# Communication_and_peripherals_ETH.net
KiCad netlist of a schematic drawn in Altium Designer
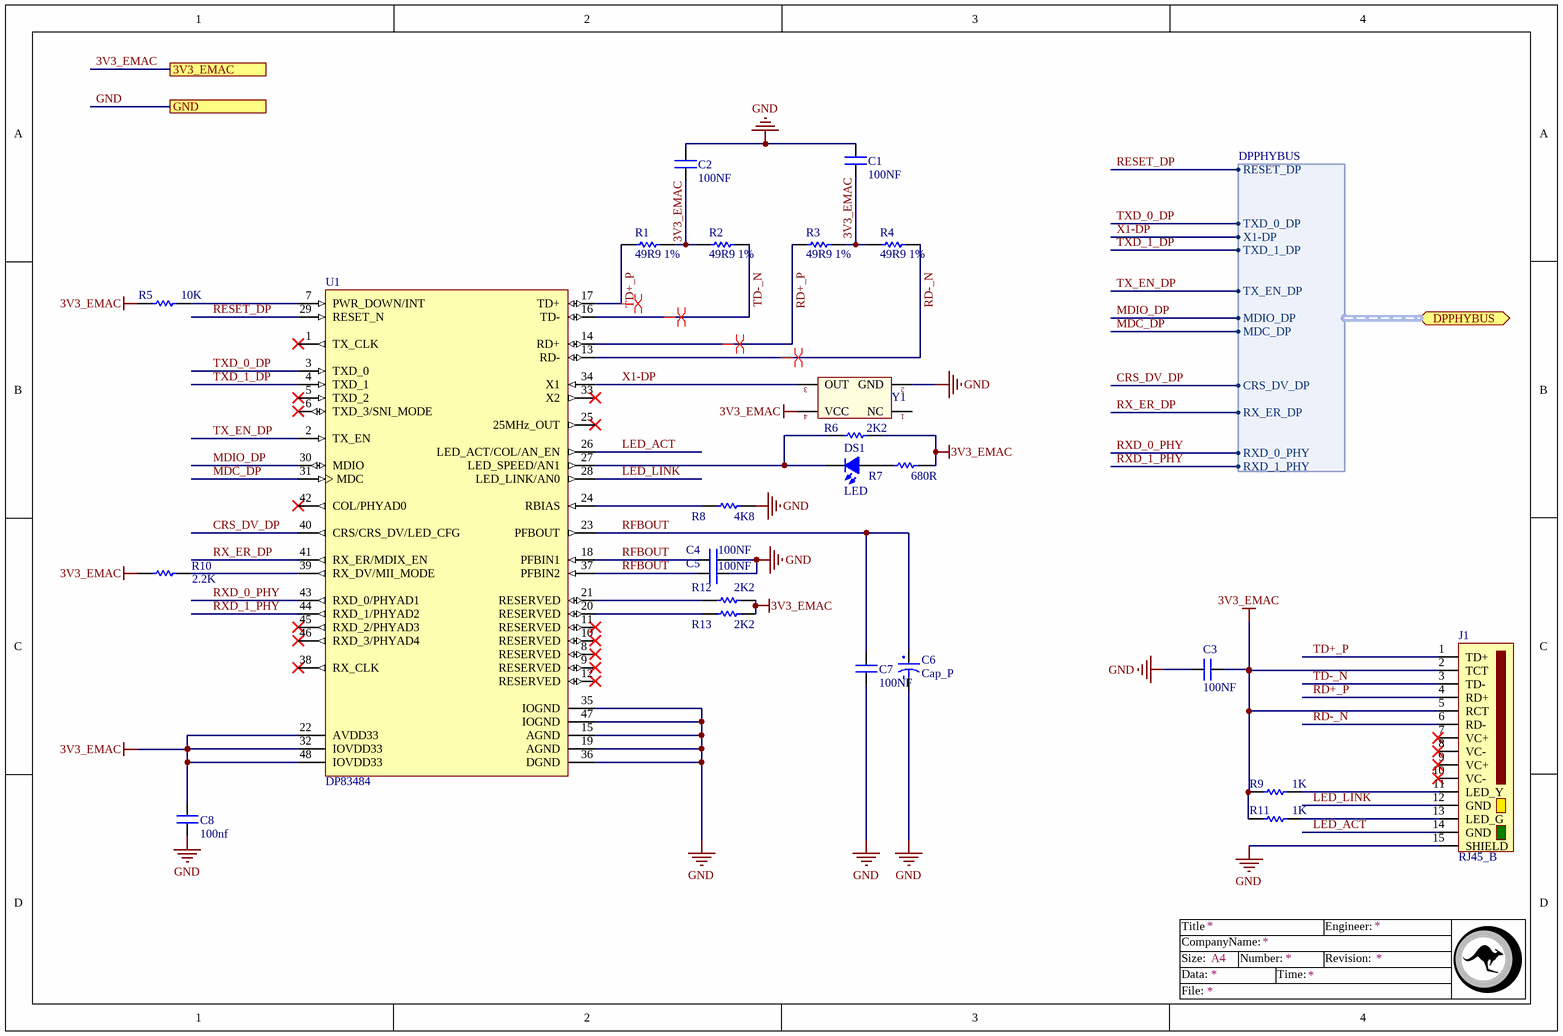
[diagram p0: Communication and peripherals ETH.SchDoc]

(export (version "E")
  (design (tool "Eeschema 10.0.6"))
  (components
    (comp (ref "C1")
      (value "100NF")
      (footprint "Cap0805")
      (description "Surface mount Capacitor")
      (libsource (lib "PMLIB2020") (part "Cap"))
    )
    (comp (ref "C2")
      (value "100NF")
      (footprint "Cap0805")
      (description "Surface mount Capacitor")
      (libsource (lib "PMLIB2020") (part "Cap"))
    )
    (comp (ref "C3")
      (value "100NF")
      (footprint "Cap0805")
      (description "Surface mount Capacitor")
      (libsource (lib "PMLIB2020") (part "Cap"))
    )
    (comp (ref "C4")
      (value "100NF")
      (footprint "Cap0805")
      (description "Surface mount Capacitor")
      (libsource (lib "PMLIB2020") (part "Cap"))
    )
    (comp (ref "C5")
      (value "100NF")
      (footprint "Cap0805")
      (description "Surface mount Capacitor")
      (libsource (lib "PMLIB2020") (part "Cap"))
    )
    (comp (ref "C6")
      (value "Cap_P")
      (footprint "Cap_4mm")
      (description "Polarity")
      (libsource (lib "PMLIB2020") (part "Cap_P"))
    )
    (comp (ref "C7")
      (value "100NF")
      (footprint "Cap0805")
      (description "Surface mount Capacitor")
      (libsource (lib "PMLIB2020") (part "Cap"))
    )
    (comp (ref "C8")
      (value "100nf")
      (footprint "Cap0805")
      (description "Surface mount Capacitor")
      (libsource (lib "PMLIB2020") (part "Cap"))
    )
    (comp (ref "DS1") (value "LED") (footprint "Led0805") (libsource (lib "PMLIB2020") (part "LED")))
    (comp (ref "J1")
      (value "RJ45_B")
      (footprint "RJ45_B")
      (description "Ethernet Connector")
      (libsource (lib "PMLIB2020") (part "RJ45_B"))
    )
    (comp (ref "R1")
      (value "49R9 1%")
      (footprint "R0805")
      (description "Resistor")
      (libsource (lib "PMLIB2020") (part "Resistor"))
    )
    (comp (ref "R2")
      (value "49R9 1%")
      (footprint "R0805")
      (description "Resistor")
      (libsource (lib "PMLIB2020") (part "Resistor"))
    )
    (comp (ref "R3")
      (value "49R9 1%")
      (footprint "R0805")
      (description "Resistor")
      (libsource (lib "PMLIB2020") (part "Resistor"))
    )
    (comp (ref "R4")
      (value "49R9 1%")
      (footprint "R0805")
      (description "Resistor")
      (libsource (lib "PMLIB2020") (part "Resistor"))
    )
    (comp (ref "R5")
      (value "10K")
      (footprint "R0805")
      (description "Resistor")
      (libsource (lib "PMLIB2020") (part "Resistor"))
    )
    (comp (ref "R6")
      (value "2K2")
      (footprint "R0805")
      (description "Resistor")
      (libsource (lib "PMLIB2020") (part "Resistor"))
    )
    (comp (ref "R7")
      (value "680R")
      (footprint "R0805")
      (description "Resistor")
      (libsource (lib "PMLIB2020") (part "Resistor"))
    )
    (comp (ref "R8")
      (value "4K8")
      (footprint "R0805")
      (description "Resistor")
      (libsource (lib "PMLIB2020") (part "Resistor"))
    )
    (comp (ref "R9")
      (value "1K")
      (footprint "R0805")
      (description "Resistor")
      (libsource (lib "PMLIB2020") (part "Resistor"))
    )
    (comp (ref "R10")
      (value "2.2K")
      (footprint "R0805")
      (description "Resistor")
      (libsource (lib "PMLIB2020") (part "Resistor"))
    )
    (comp (ref "R11")
      (value "1K")
      (footprint "R0805")
      (description "Resistor")
      (libsource (lib "PMLIB2020") (part "Resistor"))
    )
    (comp (ref "R12")
      (value "2K2")
      (footprint "R0805")
      (description "Resistor")
      (libsource (lib "PMLIB2020") (part "Resistor"))
    )
    (comp (ref "R13")
      (value "2K2")
      (footprint "R0805")
      (description "Resistor")
      (libsource (lib "PMLIB2020") (part "Resistor"))
    )
    (comp (ref "U1")
      (value "DP83484")
      (footprint "DP83484")
      (description "Ethernet PHY")
      (libsource (lib "PMLIB2020") (part "DP83484"))
    )
    (comp (ref "Y1")
      (value "Oscillator")
      (footprint "Crystall 50Mhz")
      (libsource (lib "PMLIB2020") (part "Oscillator"))
    )
  )
  (nets
    (net (code "2") (name "/CRS_DV_DP") (class "Default")
      (node (ref "U1") (pin "40") (pinfunction "CRS/CRS_DV/LED_CFG_40") (pintype "output"))
    )
    (net (code "3") (name "/LED_ACT") (class "Default")
      (node (ref "J1") (pin "14") (pinfunction "GND_14") (pintype "passive"))
      (node (ref "U1") (pin "26") (pinfunction "LED_ACT/COL/AN_EN_26") (pintype "output"))
    )
    (net (code "4") (name "/LED_LINK") (class "Default")
      (node (ref "J1") (pin "12") (pinfunction "GND_12") (pintype "passive"))
      (node (ref "U1") (pin "28") (pinfunction "LED_LINK/AN0_28") (pintype "output"))
    )
    (net (code "5") (name "/MDC_DP") (class "Default")
      (node (ref "U1") (pin "31") (pinfunction "MDC_31") (pintype "input"))
    )
    (net (code "6") (name "/MDIO_DP") (class "Default")
      (node (ref "U1") (pin "30") (pinfunction "MDIO_30") (pintype "bidirectional"))
    )
    (net (code "7") (name "/RD+_P") (class "Default")
      (node (ref "J1") (pin "4") (pinfunction "RD+_4") (pintype "passive"))
      (node (ref "R3") (pin "1") (pinfunction "1_1") (pintype "passive"))
      (node (ref "U1") (pin "14") (pinfunction "RD+_14") (pintype "bidirectional"))
    )
    (net (code "8") (name "/RD-_N") (class "Default")
      (node (ref "J1") (pin "6") (pinfunction "RD-_6") (pintype "passive"))
      (node (ref "R4") (pin "2") (pinfunction "2_2") (pintype "passive"))
      (node (ref "U1") (pin "13") (pinfunction "RD-_13") (pintype "bidirectional"))
    )
    (net (code "9") (name "/RESET_DP") (class "Default")
      (node (ref "U1") (pin "29") (pinfunction "RESET_N_29") (pintype "input"))
    )
    (net (code "10") (name "/RFBOUT") (class "Default")
      (node (ref "C4") (pin "1") (pinfunction "1_1") (pintype "passive"))
      (node (ref "C5") (pin "1") (pinfunction "1_1") (pintype "passive"))
      (node (ref "C6") (pin "2") (pinfunction "2_2") (pintype "passive"))
      (node (ref "C7") (pin "2") (pinfunction "2_2") (pintype "passive"))
      (node (ref "U1") (pin "18") (pinfunction "PFBIN1_18") (pintype "input"))
      (node (ref "U1") (pin "23") (pinfunction "PFBOUT_23") (pintype "output"))
      (node (ref "U1") (pin "37") (pinfunction "PFBIN2_37") (pintype "input"))
    )
    (net (code "11") (name "/RXD_0_PHY") (class "Default")
      (node (ref "U1") (pin "43") (pinfunction "RXD_0/PHYAD1_43") (pintype "output"))
    )
    (net (code "12") (name "/RXD_1_PHY") (class "Default")
      (node (ref "U1") (pin "44") (pinfunction "RXD_1/PHYAD2_44") (pintype "output"))
    )
    (net (code "13") (name "/RX_ER_DP") (class "Default")
      (node (ref "U1") (pin "41") (pinfunction "RX_ER/MDIX_EN_41") (pintype "output"))
    )
    (net (code "14") (name "/TD+_P") (class "Default")
      (node (ref "J1") (pin "1") (pinfunction "TD+_1") (pintype "passive"))
      (node (ref "R1") (pin "1") (pinfunction "1_1") (pintype "passive"))
      (node (ref "U1") (pin "17") (pinfunction "TD+_17") (pintype "bidirectional"))
    )
    (net (code "15") (name "/TD-_N") (class "Default")
      (node (ref "J1") (pin "3") (pinfunction "TD-_3") (pintype "passive"))
      (node (ref "R2") (pin "2") (pinfunction "2_2") (pintype "passive"))
      (node (ref "U1") (pin "16") (pinfunction "TD-_16") (pintype "bidirectional"))
    )
    (net (code "16") (name "/TXD_0_DP") (class "Default")
      (node (ref "U1") (pin "3") (pinfunction "TXD_0_3") (pintype "input"))
    )
    (net (code "17") (name "/TXD_1_DP") (class "Default")
      (node (ref "U1") (pin "4") (pinfunction "TXD_1_4") (pintype "input"))
    )
    (net (code "18") (name "/TX_EN_DP") (class "Default")
      (node (ref "U1") (pin "2") (pinfunction "TX_EN_2") (pintype "input"))
    )
    (net (code "19") (name "/X1-DP") (class "Default")
      (node (ref "U1") (pin "34") (pinfunction "X1_34") (pintype "input"))
      (node (ref "Y1") (pin "3") (pinfunction "OUT_3") (pintype "passive"))
    )
    (net (code "21") (name "3V3_EMAC") (class "Default")
      (node (ref "C1") (pin "1") (pinfunction "1_1") (pintype "passive"))
      (node (ref "C2") (pin "1") (pinfunction "1_1") (pintype "passive"))
      (node (ref "C3") (pin "1") (pinfunction "1_1") (pintype "passive"))
      (node (ref "C8") (pin "2") (pinfunction "2_2") (pintype "passive"))
      (node (ref "J1") (pin "2") (pinfunction "TCT_2") (pintype "passive"))
      (node (ref "J1") (pin "5") (pinfunction "RCT_5") (pintype "passive"))
      (node (ref "R1") (pin "2") (pinfunction "2_2") (pintype "passive"))
      (node (ref "R10") (pin "2") (pinfunction "2_2") (pintype "passive"))
      (node (ref "R11") (pin "1") (pinfunction "1_1") (pintype "passive"))
      (node (ref "R12") (pin "1") (pinfunction "1_1") (pintype "passive"))
      (node (ref "R13") (pin "1") (pinfunction "1_1") (pintype "passive"))
      (node (ref "R2") (pin "1") (pinfunction "1_1") (pintype "passive"))
      (node (ref "R3") (pin "2") (pinfunction "2_2") (pintype "passive"))
      (node (ref "R4") (pin "1") (pinfunction "1_1") (pintype "passive"))
      (node (ref "R5") (pin "2") (pinfunction "2_2") (pintype "passive"))
      (node (ref "R6") (pin "1") (pinfunction "1_1") (pintype "passive"))
      (node (ref "R7") (pin "1") (pinfunction "1_1") (pintype "passive"))
      (node (ref "R9") (pin "1") (pinfunction "1_1") (pintype "passive"))
      (node (ref "U1") (pin "22") (pinfunction "AVDD33_22") (pintype "power_in"))
      (node (ref "U1") (pin "32") (pinfunction "IOVDD33_32") (pintype "power_in"))
      (node (ref "U1") (pin "48") (pinfunction "IOVDD33_48") (pintype "power_in"))
      (node (ref "Y1") (pin "4") (pinfunction "VCC_4") (pintype "passive"))
    )
    (net (code "22") (name "GND") (class "Default")
      (node (ref "C1") (pin "2") (pinfunction "2_2") (pintype "passive"))
      (node (ref "C2") (pin "2") (pinfunction "2_2") (pintype "passive"))
      (node (ref "C3") (pin "2") (pinfunction "2_2") (pintype "passive"))
      (node (ref "C4") (pin "2") (pinfunction "2_2") (pintype "passive"))
      (node (ref "C5") (pin "2") (pinfunction "2_2") (pintype "passive"))
      (node (ref "C6") (pin "1") (pinfunction "1_1") (pintype "passive"))
      (node (ref "C7") (pin "1") (pinfunction "1_1") (pintype "passive"))
      (node (ref "C8") (pin "1") (pinfunction "1_1") (pintype "passive"))
      (node (ref "J1") (pin "15") (pinfunction "SHIELD_15") (pintype "passive"))
      (node (ref "U1") (pin "15") (pinfunction "AGND_15") (pintype "power_in"))
      (node (ref "U1") (pin "19") (pinfunction "AGND_19") (pintype "power_in"))
      (node (ref "U1") (pin "35") (pinfunction "IOGND_35") (pintype "power_in"))
      (node (ref "U1") (pin "36") (pinfunction "DGND_36") (pintype "power_in"))
      (node (ref "U1") (pin "47") (pinfunction "IOGND_47") (pintype "power_in"))
      (node (ref "Y1") (pin "2") (pinfunction "GND_2") (pintype "passive"))
    )
    (net (code "23") (name "Net-(DS1-PadA)") (class "Default")
      (node (ref "DS1") (pin "A") (pinfunction "A_A") (pintype "passive"))
      (node (ref "R7") (pin "2") (pinfunction "2_2") (pintype "passive"))
    )
    (net (code "24") (name "Net-(J1-LED_G)") (class "Default")
      (node (ref "J1") (pin "13") (pinfunction "LED_G_13") (pintype "passive"))
      (node (ref "R11") (pin "2") (pinfunction "2_2") (pintype "passive"))
    )
    (net (code "25") (name "Net-(J1-LED_Y)") (class "Default")
      (node (ref "J1") (pin "11") (pinfunction "LED_Y_11") (pintype "passive"))
      (node (ref "R9") (pin "2") (pinfunction "2_2") (pintype "passive"))
    )
    (net (code "26") (name "Net-(R12-Pad2)") (class "Default")
      (node (ref "R12") (pin "2") (pinfunction "2_2") (pintype "passive"))
      (node (ref "U1") (pin "21") (pinfunction "RESERVED_21") (pintype "bidirectional"))
    )
    (net (code "27") (name "Net-(R13-Pad2)") (class "Default")
      (node (ref "R13") (pin "2") (pinfunction "2_2") (pintype "passive"))
      (node (ref "U1") (pin "20") (pinfunction "RESERVED_20") (pintype "bidirectional"))
    )
    (net (code "28") (name "Net-(U1-LED_SPEED{slash}AN1)") (class "Default")
      (node (ref "DS1") (pin "K") (pinfunction "K_K") (pintype "passive"))
      (node (ref "R6") (pin "2") (pinfunction "2_2") (pintype "passive"))
      (node (ref "U1") (pin "27") (pinfunction "LED_SPEED/AN1_27") (pintype "output"))
    )
    (net (code "29") (name "Net-(U1-PWR_DOWN{slash}INT)") (class "Default")
      (node (ref "R5") (pin "1") (pinfunction "1_1") (pintype "passive"))
      (node (ref "U1") (pin "7") (pinfunction "PWR_DOWN/INT_7") (pintype "input"))
    )
    (net (code "30") (name "Net-(U1-RBIAS)") (class "Default")
      (node (ref "R8") (pin "2") (pinfunction "2_2") (pintype "passive"))
      (node (ref "U1") (pin "24") (pinfunction "RBIAS_24") (pintype "input"))
    )
    (net (code "31") (name "Net-(U1-RX_DV{slash}MII_MODE)") (class "Default")
      (node (ref "R10") (pin "1") (pinfunction "1_1") (pintype "passive"))
      (node (ref "U1") (pin "39") (pinfunction "RX_DV/MII_MODE_39") (pintype "output"))
    )
    (net (code "32") (name "unconnected-(J1-VC+-Pad7)") (class "Default")
      (node (ref "J1") (pin "7") (pinfunction "VC+_7") (pintype "passive+no_connect"))
    )
    (net (code "33") (name "unconnected-(J1-VC+-Pad9)") (class "Default")
      (node (ref "J1") (pin "9") (pinfunction "VC+_9") (pintype "passive+no_connect"))
    )
    (net (code "34") (name "unconnected-(J1-VC--Pad8)") (class "Default")
      (node (ref "J1") (pin "8") (pinfunction "VC-_8") (pintype "passive+no_connect"))
    )
    (net (code "35") (name "unconnected-(J1-VC--Pad10)") (class "Default")
      (node (ref "J1") (pin "10") (pinfunction "VC-_10") (pintype "passive+no_connect"))
    )
    (net (code "36") (name "unconnected-(R8-Pad1)") (class "Default")
      (node (ref "R8") (pin "1") (pinfunction "1_1") (pintype "passive"))
    )
    (net (code "37") (name "unconnected-(U1-25MHz_OUT-Pad25)") (class "Default")
      (node (ref "U1") (pin "25") (pinfunction "25MHz_OUT_25") (pintype "output+no_connect"))
    )
    (net (code "38") (name "unconnected-(U1-COL{slash}PHYAD0-Pad42)") (class "Default")
      (node (ref "U1") (pin "42") (pinfunction "COL/PHYAD0_42") (pintype "output+no_connect"))
    )
    (net (code "39") (name "unconnected-(U1-RESERVED-Pad8)") (class "Default")
      (node (ref "U1") (pin "8") (pinfunction "RESERVED_8") (pintype "bidirectional+no_connect"))
    )
    (net (code "40") (name "unconnected-(U1-RESERVED-Pad9)") (class "Default")
      (node (ref "U1") (pin "9") (pinfunction "RESERVED_9") (pintype "bidirectional+no_connect"))
    )
    (net (code "41") (name "unconnected-(U1-RESERVED-Pad10)") (class "Default")
      (node (ref "U1") (pin "10") (pinfunction "RESERVED_10") (pintype "bidirectional+no_connect"))
    )
    (net (code "42") (name "unconnected-(U1-RESERVED-Pad11)") (class "Default")
      (node (ref "U1") (pin "11") (pinfunction "RESERVED_11") (pintype "bidirectional+no_connect"))
    )
    (net (code "43") (name "unconnected-(U1-RESERVED-Pad12)") (class "Default")
      (node (ref "U1") (pin "12") (pinfunction "RESERVED_12") (pintype "bidirectional+no_connect"))
    )
    (net (code "44") (name "unconnected-(U1-RXD_2{slash}PHYAD3-Pad45)") (class "Default")
      (node (ref "U1") (pin "45") (pinfunction "RXD_2/PHYAD3_45") (pintype "output+no_connect"))
    )
    (net (code "45") (name "unconnected-(U1-RXD_3{slash}PHYAD4-Pad46)") (class "Default")
      (node (ref "U1") (pin "46") (pinfunction "RXD_3/PHYAD4_46") (pintype "output+no_connect"))
    )
    (net (code "46") (name "unconnected-(U1-RX_CLK-Pad38)") (class "Default")
      (node (ref "U1") (pin "38") (pinfunction "RX_CLK_38") (pintype "output+no_connect"))
    )
    (net (code "47") (name "unconnected-(U1-TXD_2-Pad5)") (class "Default")
      (node (ref "U1") (pin "5") (pinfunction "TXD_2_5") (pintype "input+no_connect"))
    )
    (net (code "48") (name "unconnected-(U1-TXD_3{slash}SNI_MODE-Pad6)") (class "Default")
      (node (ref "U1") (pin "6") (pinfunction "TXD_3/SNI_MODE_6") (pintype "bidirectional+no_connect"))
    )
    (net (code "49") (name "unconnected-(U1-TX_CLK-Pad1)") (class "Default")
      (node (ref "U1") (pin "1") (pinfunction "TX_CLK_1") (pintype "output+no_connect"))
    )
    (net (code "50") (name "unconnected-(U1-X2-Pad33)") (class "Default")
      (node (ref "U1") (pin "33") (pinfunction "X2_33") (pintype "output+no_connect"))
    )
    (net (code "51") (name "unconnected-(Y1-NC-Pad1)") (class "Default")
      (node (ref "Y1") (pin "1") (pinfunction "NC_1") (pintype "passive"))
    )
  )
)
